# breadboard_power_supply_2nd.net
KiCad netlist of a schematic drawn in EAGLE
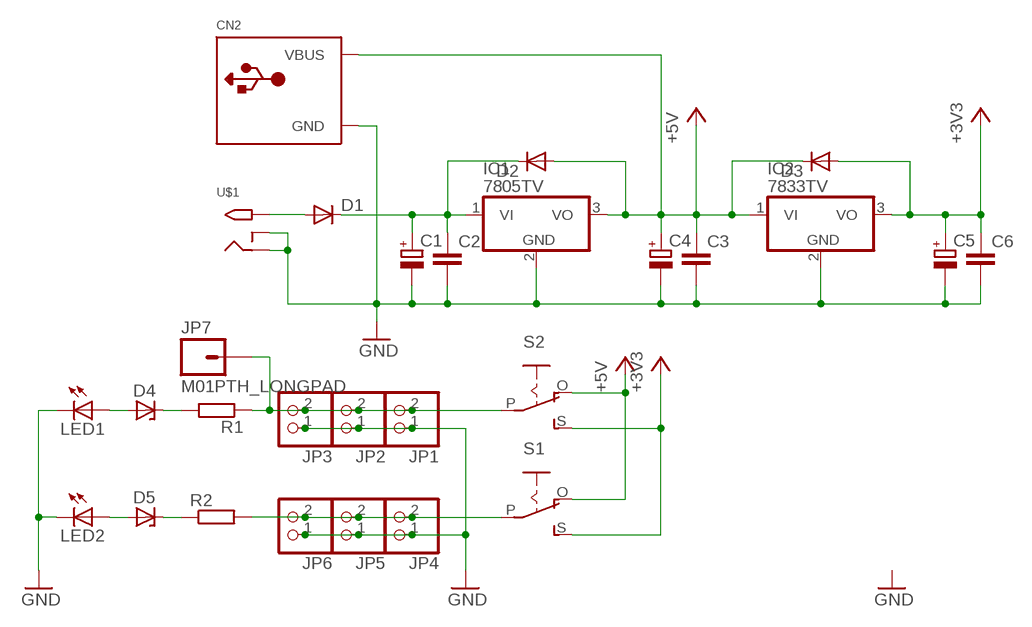
[diagram p0: schematic, sheet 1]

(export (version "E")
  (design (tool "Eeschema 10.0.6"))
  (components
    (comp (ref "C1")
      (value "CPOL-EUE2.5-6")
      (footprint "eagle-import:E2,5-6")
      (libsource (lib "eagle-import") (part "CPOL-EUE2.5-6"))
    )
    (comp (ref "C2")
      (value "C-EU025-025X050")
      (footprint "eagle-import:C025-025X050")
      (libsource (lib "eagle-import") (part "C-EU025-025X050"))
    )
    (comp (ref "C3")
      (value "C-EU025-025X050")
      (footprint "eagle-import:C025-025X050")
      (libsource (lib "eagle-import") (part "C-EU025-025X050"))
    )
    (comp (ref "C4")
      (value "CPOL-EUE2.5-6")
      (footprint "eagle-import:E2,5-6")
      (libsource (lib "eagle-import") (part "CPOL-EUE2.5-6"))
    )
    (comp (ref "C5")
      (value "CPOL-EUE2.5-6")
      (footprint "eagle-import:E2,5-6")
      (libsource (lib "eagle-import") (part "CPOL-EUE2.5-6"))
    )
    (comp (ref "C6")
      (value "C-EU025-025X050")
      (footprint "eagle-import:C025-025X050")
      (libsource (lib "eagle-import") (part "C-EU025-025X050"))
    )
    (comp (ref "CN2")
      (value "USB")
      (footprint "eagle-import:USB-MINIB-THM")
      (libsource (lib "eagle-import") (part "USB"))
    )
    (comp (ref "D1")
      (value "DIODE-D-5")
      (footprint "eagle-import:D-5")
      (libsource (lib "eagle-import") (part "DIODE-D-5"))
    )
    (comp (ref "D2")
      (value "DIODE-D-5")
      (footprint "eagle-import:D-5")
      (libsource (lib "eagle-import") (part "DIODE-D-5"))
    )
    (comp (ref "D3")
      (value "DIODE-D-5")
      (footprint "eagle-import:D-5")
      (libsource (lib "eagle-import") (part "DIODE-D-5"))
    )
    (comp (ref "D4")
      (value "ZENER-DIODEZD-2.5")
      (footprint "eagle-import:ZDIO-2.5")
      (libsource (lib "eagle-import") (part "ZENER-DIODEZD-2.5"))
    )
    (comp (ref "D5")
      (value "ZENER-DIODEZD-2.5")
      (footprint "eagle-import:ZDIO-2.5")
      (libsource (lib "eagle-import") (part "ZENER-DIODEZD-2.5"))
    )
    (comp (ref "IC1")
      (value "7805TV")
      (footprint "eagle-import:TO220V")
      (libsource (lib "eagle-import") (part "78TV05"))
    )
    (comp (ref "IC2")
      (value "7833TV")
      (footprint "eagle-import:TO220V")
      (libsource (lib "eagle-import") (part "78TV05"))
    )
    (comp (ref "JP1")
      (value "PINHD-1X2")
      (footprint "eagle-import:1X02")
      (libsource (lib "eagle-import") (part "PINHD-1X2"))
    )
    (comp (ref "JP2")
      (value "PINHD-1X2")
      (footprint "eagle-import:1X02")
      (libsource (lib "eagle-import") (part "PINHD-1X2"))
    )
    (comp (ref "JP3")
      (value "PINHD-1X2")
      (footprint "eagle-import:1X02")
      (libsource (lib "eagle-import") (part "PINHD-1X2"))
    )
    (comp (ref "JP4")
      (value "PINHD-1X2")
      (footprint "eagle-import:1X02")
      (libsource (lib "eagle-import") (part "PINHD-1X2"))
    )
    (comp (ref "JP5")
      (value "PINHD-1X2")
      (footprint "eagle-import:1X02")
      (libsource (lib "eagle-import") (part "PINHD-1X2"))
    )
    (comp (ref "JP6")
      (value "PINHD-1X2")
      (footprint "eagle-import:1X02")
      (libsource (lib "eagle-import") (part "PINHD-1X2"))
    )
    (comp (ref "JP7")
      (value "M01PTH_LONGPAD")
      (footprint "eagle-import:1X01_LONGPAD")
      (libsource (lib "eagle-import") (part "M01PTH_LONGPAD"))
    )
    (comp (ref "LED1")
      (value "LED3MM")
      (footprint "eagle-import:LED3MM")
      (libsource (lib "eagle-import") (part "LED3MM"))
    )
    (comp (ref "LED2")
      (value "LED3MM")
      (footprint "eagle-import:LED3MM")
      (libsource (lib "eagle-import") (part "LED3MM"))
    )
    (comp (ref "R1")
      (value "R-EU_0204/2V")
      (footprint "eagle-import:0204V")
      (libsource (lib "eagle-import") (part "R-EU_0204/2V"))
    )
    (comp (ref "R2")
      (value "R-EU_0204/2V")
      (footprint "eagle-import:0204V")
      (libsource (lib "eagle-import") (part "R-EU_0204/2V"))
    )
    (comp (ref "S1")
      (value "EG1218S")
      (footprint "eagle-import:EG1218")
      (libsource (lib "eagle-import") (part "EG1218S"))
    )
    (comp (ref "S2")
      (value "EG1218S")
      (footprint "eagle-import:EG1218")
      (libsource (lib "eagle-import") (part "EG1218S"))
    )
    (comp (ref "U$1")
      (value "2.1MMJACKTHM")
      (footprint "eagle-import:PJ-102A")
      (libsource (lib "eagle-import") (part "2.1MMJACKTHM"))
    )
  )
  (nets
    (net (code "1") (name "+3V3") (class "Default")
      (node (ref "C5") (pin "+") (pinfunction "+_+") (pintype "passive"))
      (node (ref "C6") (pin "1") (pinfunction "1_1") (pintype "passive"))
      (node (ref "D3") (pin "A") (pinfunction "A_A") (pintype "passive"))
      (node (ref "IC2") (pin "3") (pinfunction "VO_3") (pintype "passive"))
      (node (ref "S1") (pin "S") (pinfunction "S_S") (pintype "passive"))
      (node (ref "S2") (pin "S") (pinfunction "S_S") (pintype "passive"))
    )
    (net (code "2") (name "+5V") (class "Default")
      (node (ref "C3") (pin "1") (pinfunction "1_1") (pintype "passive"))
      (node (ref "C4") (pin "+") (pinfunction "+_+") (pintype "passive"))
      (node (ref "CN2") (pin "VBUS") (pinfunction "VBUS_VBUS") (pintype "power_in"))
      (node (ref "D2") (pin "A") (pinfunction "A_A") (pintype "passive"))
      (node (ref "D3") (pin "C") (pinfunction "C_C") (pintype "passive"))
      (node (ref "IC1") (pin "3") (pinfunction "VO_3") (pintype "passive"))
      (node (ref "IC2") (pin "1") (pinfunction "VI_1") (pintype "input"))
      (node (ref "S1") (pin "O") (pinfunction "O_O") (pintype "passive"))
      (node (ref "S2") (pin "O") (pinfunction "O_O") (pintype "passive"))
    )
    (net (code "3") (name "GND") (class "Default")
      (node (ref "C1") (pin "-") (pinfunction "-_-") (pintype "passive"))
      (node (ref "C2") (pin "2") (pinfunction "2_2") (pintype "passive"))
      (node (ref "C3") (pin "2") (pinfunction "2_2") (pintype "passive"))
      (node (ref "C4") (pin "-") (pinfunction "-_-") (pintype "passive"))
      (node (ref "C5") (pin "-") (pinfunction "-_-") (pintype "passive"))
      (node (ref "C6") (pin "2") (pinfunction "2_2") (pintype "passive"))
      (node (ref "CN2") (pin "GND") (pinfunction "GND_GND") (pintype "power_in"))
      (node (ref "IC1") (pin "2") (pinfunction "GND_2") (pintype "passive"))
      (node (ref "IC2") (pin "2") (pinfunction "GND_2") (pintype "passive"))
      (node (ref "JP1") (pin "1") (pinfunction "1_1") (pintype "passive"))
      (node (ref "JP2") (pin "1") (pinfunction "1_1") (pintype "passive"))
      (node (ref "JP3") (pin "1") (pinfunction "1_1") (pintype "passive"))
      (node (ref "JP4") (pin "1") (pinfunction "1_1") (pintype "passive"))
      (node (ref "JP5") (pin "1") (pinfunction "1_1") (pintype "passive"))
      (node (ref "JP6") (pin "1") (pinfunction "1_1") (pintype "passive"))
      (node (ref "LED1") (pin "K") (pinfunction "C_K") (pintype "passive"))
      (node (ref "LED2") (pin "K") (pinfunction "C_K") (pintype "passive"))
      (node (ref "U$1") (pin "RING") (pinfunction "RING_RING") (pintype "bidirectional"))
      (node (ref "U$1") (pin "RING_SW") (pinfunction "RING_SW_RING_SW") (pintype "bidirectional"))
    )
    (net (code "4") (name "Net-(D1-PadA)") (class "Default")
      (node (ref "D1") (pin "A") (pinfunction "A_A") (pintype "passive"))
      (node (ref "U$1") (pin "TIP") (pinfunction "TIP_TIP") (pintype "bidirectional"))
    )
    (net (code "5") (name "Net-(D4-PadA)") (class "Default")
      (node (ref "D4") (pin "A") (pinfunction "A_A") (pintype "passive"))
      (node (ref "LED1") (pin "A") (pinfunction "A_A") (pintype "passive"))
    )
    (net (code "6") (name "Net-(D4-PadC)") (class "Default")
      (node (ref "D4") (pin "C") (pinfunction "C_C") (pintype "passive"))
      (node (ref "R1") (pin "2") (pinfunction "2_2") (pintype "passive"))
    )
    (net (code "7") (name "Net-(D5-PadA)") (class "Default")
      (node (ref "D5") (pin "A") (pinfunction "A_A") (pintype "passive"))
      (node (ref "LED2") (pin "A") (pinfunction "A_A") (pintype "passive"))
    )
    (net (code "8") (name "Net-(D5-PadC)") (class "Default")
      (node (ref "D5") (pin "C") (pinfunction "C_C") (pintype "passive"))
      (node (ref "R2") (pin "1") (pinfunction "1_1") (pintype "passive"))
    )
    (net (code "9") (name "Net-(IC1-VI)") (class "Default")
      (node (ref "C1") (pin "+") (pinfunction "+_+") (pintype "passive"))
      (node (ref "C2") (pin "1") (pinfunction "1_1") (pintype "passive"))
      (node (ref "D1") (pin "C") (pinfunction "C_C") (pintype "passive"))
      (node (ref "D2") (pin "C") (pinfunction "C_C") (pintype "passive"))
      (node (ref "IC1") (pin "1") (pinfunction "VI_1") (pintype "input"))
    )
    (net (code "10") (name "Net-(JP1-Pad2)") (class "Default")
      (node (ref "JP1") (pin "2") (pinfunction "2_2") (pintype "passive"))
      (node (ref "JP2") (pin "2") (pinfunction "2_2") (pintype "passive"))
      (node (ref "JP3") (pin "2") (pinfunction "2_2") (pintype "passive"))
      (node (ref "JP7") (pin "1") (pinfunction "1_1") (pintype "passive"))
      (node (ref "R1") (pin "1") (pinfunction "1_1") (pintype "passive"))
      (node (ref "S2") (pin "P") (pinfunction "P_P") (pintype "passive"))
    )
    (net (code "11") (name "Net-(JP4-Pad2)") (class "Default")
      (node (ref "JP4") (pin "2") (pinfunction "2_2") (pintype "passive"))
      (node (ref "JP5") (pin "2") (pinfunction "2_2") (pintype "passive"))
      (node (ref "JP6") (pin "2") (pinfunction "2_2") (pintype "passive"))
      (node (ref "R2") (pin "2") (pinfunction "2_2") (pintype "passive"))
      (node (ref "S1") (pin "P") (pinfunction "P_P") (pintype "passive"))
    )
  )
)
